# current_stabilizer.net
KiCad netlist of a schematic drawn in Altium Designer
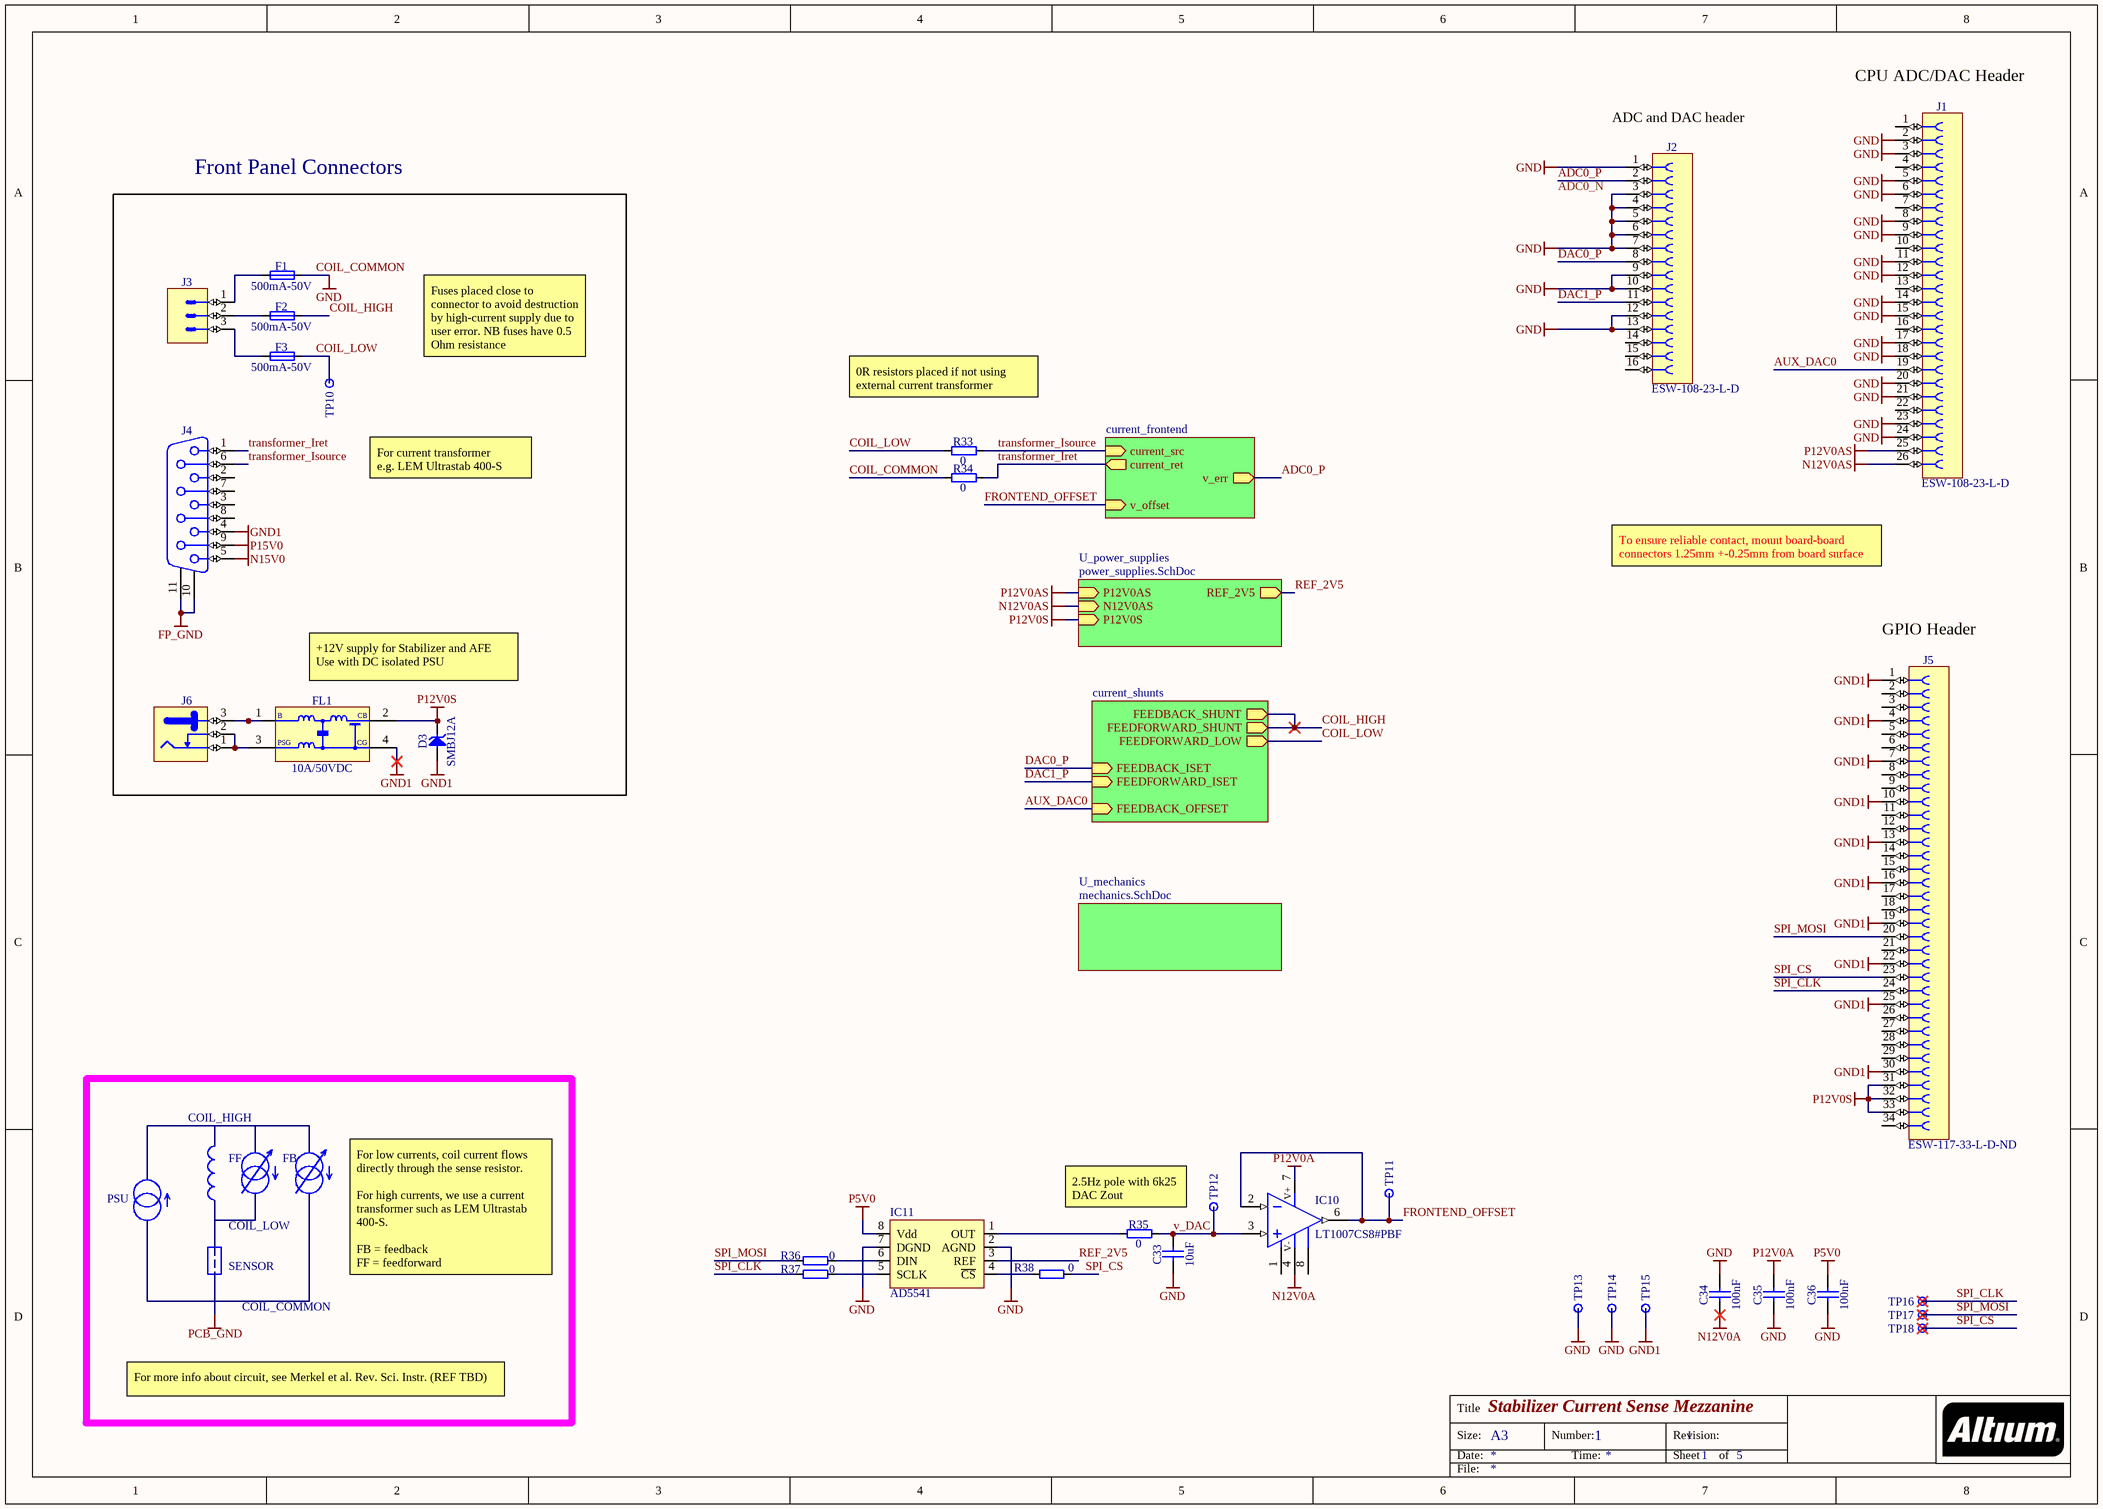
[diagram p0: current_stabilizer.SchDoc]

(export (version "E")
  (design (tool "Eeschema 10.0.6"))
  (components
    (comp (ref "C33")
      (value "10uF")
      (footprint "CAPC2012X95N")
      (description "Non-polarised capacitor")
      (fields
        (field (name "PART NUMBER") "CC0805_10UF_25V_10%_X5R")
        (field (name "VOLTAGE") "25V")
        (field (name "AUTHOR") "CERN DEM JLC")
      )
      (libsource (lib "Capacitors") (part "Capacitor - non polarized"))
    )
    (comp (ref "C34")
      (value "100nF")
      (footprint "CAPC1608X87N")
      (description "Non-polarised capacitor")
      (fields
        (field (name "PART NUMBER") "CC0603_100NF_50V_10%_X7R")
        (field (name "VOLTAGE") "50V")
        (field (name "AUTHOR") "CERN DEM JLC")
      )
      (libsource (lib "Capacitors") (part "Capacitor - non polarized"))
    )
    (comp (ref "C35")
      (value "100nF")
      (footprint "CAPC1608X87N")
      (description "Non-polarised capacitor")
      (fields
        (field (name "PART NUMBER") "CC0603_100NF_50V_10%_X7R")
        (field (name "VOLTAGE") "50V")
        (field (name "AUTHOR") "CERN DEM JLC")
      )
      (libsource (lib "Capacitors") (part "Capacitor - non polarized"))
    )
    (comp (ref "C36")
      (value "100nF")
      (footprint "CAPC1608X87N")
      (description "Non-polarised capacitor")
      (fields
        (field (name "PART NUMBER") "CC0603_100NF_50V_10%_X7R")
        (field (name "VOLTAGE") "50V")
        (field (name "AUTHOR") "CERN DEM JLC")
      )
      (libsource (lib "Capacitors") (part "Capacitor - non polarized"))
    )
    (comp (ref "D3")
      (value "SMBJ12A")
      (footprint "DIOM5336X265N")
      (description "Zener Diode")
      (fields
        (field (name "VOLTAGE") "12V")
        (field (name "POWER") "600W")
        (field (name "AUTHOR") "CERN DEM JLC")
      )
      (libsource (lib "ICs And Semiconductors") (part "Diode Zener"))
    )
    (comp (ref "F1")
      (value "500mA-50V")
      (footprint "FUSC1608X55N")
      (description "Fuse")
      (fields
        (field (name "PART NUMBER") "FUS0603_BOURNS-SF-0603F050-2")
        (field (name "MANUFACTURER") "BOURNS")
        (field (name "AUTHOR") "CERN DEM JLC")
      )
      (libsource (lib "Eletro-mechanical") (part "Fuse"))
    )
    (comp (ref "F2")
      (value "500mA-50V")
      (footprint "FUSC1608X55N")
      (description "Fuse")
      (fields
        (field (name "PART NUMBER") "FUS0603_BOURNS-SF-0603F050-2")
        (field (name "MANUFACTURER") "BOURNS")
        (field (name "AUTHOR") "CERN DEM JLC")
      )
      (libsource (lib "Eletro-mechanical") (part "Fuse"))
    )
    (comp (ref "F3")
      (value "500mA-50V")
      (footprint "FUSC1608X55N")
      (description "Fuse")
      (fields
        (field (name "PART NUMBER") "FUS0603_BOURNS-SF-0603F050-2")
        (field (name "MANUFACTURER") "BOURNS")
        (field (name "AUTHOR") "CERN DEM JLC")
      )
      (libsource (lib "Eletro-mechanical") (part "Fuse"))
    )
    (comp (ref "FL1")
      (value "10A/50VDC")
      (footprint "FIL_MURATA_BNX02")
      (description "Block Type EMIFIL (LC Combined)")
      (fields
        (field (name "PART NUMBER") "FIL_MURATA_BNX022-01L")
        (field (name "MANUFACTURER") "MURATA")
        (field (name "AUTHOR") "CERN DEM JLC")
      )
      (libsource (lib "Inductors & Transformers") (part "FIL_MURATA_BNX02"))
    )
    (comp (ref "IC10")
      (value "LT1007CS8#PBF")
      (footprint "SOIC127P600X175-8N")
      (description "Operational Amplifier with Offset 1-8")
      (fields (field (name "MANUFACTURER") "LINEAR TECHNOLOGY") (field (name "AUTHOR") "CERN DEM JLC"))
      (libsource (lib "ICs And Semiconductors") (part "Operational Amplifier Type3"))
    )
    (comp (ref "IC11")
      (value "AD5541")
      (footprint "library_ICs:so-8")
      (description "16 bit serial DAC")
      (fields
        (field (name "MANUFACTURER") "ANALOG DEVICES")
        (field (name "MANUFACTURER PART NUMBER") "AD5541LRZ")
      )
      (libsource (lib "LIBRARY_SCH") (part "AD5541LRZ"))
    )
    (comp (ref "J1")
      (value "ESW-108-23-L-D")
      (footprint "connectors:ESW-113-23-L-D")
      (description "Connector Elevated Socket 26 POS 2.54mm, 13.59mm height")
      (fields
        (field (name "MANUFACTURER") "Samtec")
        (field (name "MANUFACTURER PART NUMBER") "ESW-108-23-L-D")
      )
      (libsource (lib "connectors") (part "ESW-113-23-L-D"))
    )
    (comp (ref "J2")
      (value "ESW-108-23-L-D")
      (footprint "connectors:ESW-108-23-L-D")
      (description "Connector Elevated Socket 16 POS 2.54mm, 13.59mm height")
      (fields
        (field (name "MANUFACTURER") "Samtec")
        (field (name "MANUFACTURER PART NUMBER") "ESW-108-23-L-D")
      )
      (libsource (lib "connectors") (part "ESW-108-23-L-D"))
    )
    (comp (ref "J3")
      (value "MSTBA")
      (footprint "PHOENIX_1757255")
      (description "Connector 3 Male")
      (fields
        (field (name "PART NUMBER") "PHOENIX_1757255")
        (field (name "MANUFACTURER") "PHOENIX CONTACT")
        (field (name "AUTHOR") "CERN DEM JLC")
      )
      (libsource (lib "Connectors") (part "Connector 3 Male"))
    )
    (comp (ref "J4")
      (value "D-Sub 9F")
      (footprint "FCI_D09S13A4GV00LF")
      (description "Connector D-sub 9 Female")
      (fields
        (field (name "PART NUMBER") "FCI_D09S13A4GV00LF")
        (field (name "MANUFACTURER") "FCI")
        (field (name "AUTHOR") "CERN DEM JLC")
      )
      (libsource (lib "Connectors") (part "Connector D-sub 9 Female"))
    )
    (comp (ref "J5")
      (value "ESW-108-23-L-D")
      (footprint "connectors:ESW-117-23-L-D")
      (description "Connector Elevated Socket 34 POS 2.54mm, 13.59mm height")
      (fields
        (field (name "MANUFACTURER") "Samtec")
        (field (name "MANUFACTURER PART NUMBER") "ESW-117-33-L-D-ND")
      )
      (libsource (lib "connectors") (part "ESW-117-23-L-D"))
    )
    (comp (ref "J6")
      (value "Jack")
      (footprint "Library-connectors:SWITCHCRAFT_L712RA")
      (description "24V /3. 5A, 2.1mm Diameter Pin, SMD DC Power Supply Connector With  Break Contact")
      (fields
        (field (name "PART NUMBER") "SWITCHCRAFT_L712RA")
        (field (name "MANUFACTURER") "SWITCHCRAFT")
        (field (name "AUTHOR") "GK")
      )
      (libsource (lib "LIBRARY_SCH") (part "CON_DC_5A_THT_RA"))
    )
    (comp (ref "R33")
      (value "0")
      (footprint "RESC1608X55N")
      (description "Resistor")
      (fields
        (field (name "PART NUMBER") "R0603_0R_JUMPER")
        (field (name "MANUFACTURER") "GENERIC")
        (field (name "AUTHOR") "CERN DEM JLC")
      )
      (libsource (lib "Resistors") (part "Resistor"))
    )
    (comp (ref "R34")
      (value "0")
      (footprint "RESC1608X55N")
      (description "Resistor")
      (fields
        (field (name "PART NUMBER") "R0603_0R_JUMPER")
        (field (name "MANUFACTURER") "GENERIC")
        (field (name "AUTHOR") "CERN DEM JLC")
      )
      (libsource (lib "Resistors") (part "Resistor"))
    )
    (comp (ref "R35")
      (value "0")
      (footprint "RESC1608X55N")
      (description "Resistor")
      (fields
        (field (name "PART NUMBER") "R0603_0R_JUMPER")
        (field (name "MANUFACTURER") "GENERIC")
        (field (name "AUTHOR") "CERN DEM JLC")
      )
      (libsource (lib "Resistors") (part "Resistor"))
    )
    (comp (ref "R36")
      (value "0")
      (footprint "RESC1608X55N")
      (description "Resistor")
      (fields
        (field (name "PART NUMBER") "R0603_0R_JUMPER")
        (field (name "MANUFACTURER") "GENERIC")
        (field (name "AUTHOR") "CERN DEM JLC")
      )
      (libsource (lib "Resistors") (part "Resistor"))
    )
    (comp (ref "R37")
      (value "0")
      (footprint "RESC1608X55N")
      (description "Resistor")
      (fields
        (field (name "PART NUMBER") "R0603_0R_JUMPER")
        (field (name "MANUFACTURER") "GENERIC")
        (field (name "AUTHOR") "CERN DEM JLC")
      )
      (libsource (lib "Resistors") (part "Resistor"))
    )
    (comp (ref "R38")
      (value "0")
      (footprint "RESC1608X55N")
      (description "Resistor")
      (fields
        (field (name "PART NUMBER") "R0603_0R_JUMPER")
        (field (name "MANUFACTURER") "GENERIC")
        (field (name "AUTHOR") "CERN DEM JLC")
      )
      (libsource (lib "Resistors") (part "Resistor"))
    )
    (comp (ref "TP10")
      (value "Test Point")
      (footprint "TPS127")
      (fields (field (name "PART NUMBER") "SMD_PAD_1.27X1.27MM") (field (name "AUTHOR") "CERN DEM JLC"))
      (libsource (lib "Eletro-mechanical") (part "Test Point"))
    )
    (comp (ref "TP11")
      (value "Test Point")
      (footprint "TPS127")
      (fields (field (name "PART NUMBER") "SMD_PAD_1.27X1.27MM") (field (name "AUTHOR") "CERN DEM JLC"))
      (libsource (lib "Eletro-mechanical") (part "Test Point"))
    )
    (comp (ref "TP12")
      (value "Test Point")
      (footprint "TPS127")
      (fields (field (name "PART NUMBER") "SMD_PAD_1.27X1.27MM") (field (name "AUTHOR") "CERN DEM JLC"))
      (libsource (lib "Eletro-mechanical") (part "Test Point"))
    )
    (comp (ref "TP13")
      (value "Test Point")
      (footprint "TPS127")
      (fields (field (name "PART NUMBER") "SMD_PAD_1.27X1.27MM") (field (name "AUTHOR") "CERN DEM JLC"))
      (libsource (lib "Eletro-mechanical") (part "Test Point"))
    )
    (comp (ref "TP14")
      (value "Test Point")
      (footprint "TPS127")
      (fields (field (name "PART NUMBER") "SMD_PAD_1.27X1.27MM") (field (name "AUTHOR") "CERN DEM JLC"))
      (libsource (lib "Eletro-mechanical") (part "Test Point"))
    )
    (comp (ref "TP15")
      (value "Test Point")
      (footprint "TPS127")
      (fields (field (name "PART NUMBER") "SMD_PAD_1.27X1.27MM") (field (name "AUTHOR") "CERN DEM JLC"))
      (libsource (lib "Eletro-mechanical") (part "Test Point"))
    )
    (comp (ref "TP16")
      (value "Test Point")
      (footprint "TPS127")
      (fields (field (name "PART NUMBER") "SMD_PAD_1.27X1.27MM") (field (name "AUTHOR") "CERN DEM JLC"))
      (libsource (lib "Eletro-mechanical") (part "Test Point"))
    )
    (comp (ref "TP17")
      (value "Test Point")
      (footprint "TPS127")
      (fields (field (name "PART NUMBER") "SMD_PAD_1.27X1.27MM") (field (name "AUTHOR") "CERN DEM JLC"))
      (libsource (lib "Eletro-mechanical") (part "Test Point"))
    )
    (comp (ref "TP18")
      (value "Test Point")
      (footprint "TPS127")
      (fields (field (name "PART NUMBER") "SMD_PAD_1.27X1.27MM") (field (name "AUTHOR") "CERN DEM JLC"))
      (libsource (lib "Eletro-mechanical") (part "Test Point"))
    )
  )
  (nets
    (net (code "1") (name "/ADC0_P") (class "Default")
      (node (ref "J2") (pin "2") (pinfunction "2_2") (pintype "bidirectional"))
    )
    (net (code "2") (name "/AUX_DAC0") (class "Default")
      (node (ref "J1") (pin "19") (pinfunction "19_19") (pintype "bidirectional"))
    )
    (net (code "3") (name "/COIL_HIGH") (class "Default")
      (node (ref "F2") (pin "1") (pinfunction "1_1") (pintype "passive+no_connect"))
    )
    (net (code "4") (name "/COIL_LOW") (class "Default")
      (node (ref "F3") (pin "1") (pinfunction "1_1") (pintype "passive"))
      (node (ref "R33") (pin "1") (pinfunction "1_1") (pintype "passive"))
      (node (ref "TP10") (pin "1") (pinfunction "1_1") (pintype "bidirectional"))
    )
    (net (code "5") (name "/DAC0_P") (class "Default")
      (node (ref "J2") (pin "8") (pinfunction "8_8") (pintype "bidirectional"))
    )
    (net (code "6") (name "/DAC1_P") (class "Default")
      (node (ref "J2") (pin "11") (pinfunction "11_11") (pintype "bidirectional"))
    )
    (net (code "7") (name "/FRONTEND_OFFSET") (class "Default")
      (node (ref "IC10") (pin "2") (pinfunction "IN-_2") (pintype "input"))
      (node (ref "IC10") (pin "6") (pinfunction "OUT_6") (pintype "output"))
      (node (ref "TP11") (pin "1") (pinfunction "1_1") (pintype "bidirectional"))
    )
    (net (code "8") (name "/REF_2V5") (class "Default")
      (node (ref "IC11") (pin "3") (pinfunction "REF_3") (pintype "passive"))
    )
    (net (code "9") (name "/SPI_CLK") (class "Default")
      (node (ref "J5") (pin "24") (pinfunction "24_24") (pintype "bidirectional"))
      (node (ref "R37") (pin "1") (pinfunction "1_1") (pintype "passive"))
      (node (ref "TP16") (pin "1") (pinfunction "1_1") (pintype "bidirectional"))
    )
    (net (code "10") (name "/SPI_CS") (class "Default")
      (node (ref "J5") (pin "23") (pinfunction "23_23") (pintype "bidirectional"))
      (node (ref "R38") (pin "2") (pinfunction "2_2") (pintype "passive"))
      (node (ref "TP18") (pin "1") (pinfunction "1_1") (pintype "bidirectional"))
    )
    (net (code "11") (name "/SPI_MOSI") (class "Default")
      (node (ref "J5") (pin "20") (pinfunction "20_20") (pintype "bidirectional"))
      (node (ref "R36") (pin "1") (pinfunction "1_1") (pintype "passive"))
      (node (ref "TP17") (pin "1") (pinfunction "1_1") (pintype "bidirectional"))
    )
    (net (code "12") (name "/transformer_Iret") (class "Default")
      (node (ref "J4") (pin "1") (pinfunction "1_1") (pintype "bidirectional"))
      (node (ref "R34") (pin "2") (pinfunction "2_2") (pintype "passive"))
    )
    (net (code "13") (name "/transformer_Isource") (class "Default")
      (node (ref "J4") (pin "6") (pinfunction "6_6") (pintype "bidirectional"))
      (node (ref "R33") (pin "2") (pinfunction "2_2") (pintype "passive"))
    )
    (net (code "14") (name "/v_DAC") (class "Default")
      (node (ref "C33") (pin "2") (pinfunction "2_2") (pintype "passive"))
      (node (ref "IC10") (pin "3") (pinfunction "IN+_3") (pintype "input"))
      (node (ref "R35") (pin "2") (pinfunction "2_2") (pintype "passive"))
      (node (ref "TP12") (pin "1") (pinfunction "1_1") (pintype "bidirectional"))
    )
    (net (code "15") (name "FP_GND") (class "Default")
      (node (ref "J4") (pin "10") (pinfunction "10_10") (pintype "passive"))
      (node (ref "J4") (pin "11") (pinfunction "11_11") (pintype "passive"))
    )
    (net (code "16") (name "GND") (class "Default")
      (node (ref "C33") (pin "1") (pinfunction "1_1") (pintype "passive"))
      (node (ref "C34") (pin "2") (pinfunction "2_2") (pintype "passive"))
      (node (ref "C35") (pin "1") (pinfunction "1_1") (pintype "passive"))
      (node (ref "C36") (pin "1") (pinfunction "1_1") (pintype "passive"))
      (node (ref "F1") (pin "1") (pinfunction "1_1") (pintype "passive"))
      (node (ref "IC11") (pin "2") (pinfunction "AGND_2") (pintype "passive"))
      (node (ref "IC11") (pin "7") (pinfunction "DGND_7") (pintype "passive"))
      (node (ref "J1") (pin "11") (pinfunction "11_11") (pintype "bidirectional"))
      (node (ref "J1") (pin "12") (pinfunction "12_12") (pintype "bidirectional"))
      (node (ref "J1") (pin "14") (pinfunction "14_14") (pintype "bidirectional"))
      (node (ref "J1") (pin "15") (pinfunction "15_15") (pintype "bidirectional"))
      (node (ref "J1") (pin "17") (pinfunction "17_17") (pintype "bidirectional"))
      (node (ref "J1") (pin "18") (pinfunction "18_18") (pintype "bidirectional"))
      (node (ref "J1") (pin "2") (pinfunction "2_2") (pintype "bidirectional"))
      (node (ref "J1") (pin "20") (pinfunction "20_20") (pintype "bidirectional"))
      (node (ref "J1") (pin "21") (pinfunction "21_21") (pintype "bidirectional"))
      (node (ref "J1") (pin "23") (pinfunction "23_23") (pintype "bidirectional"))
      (node (ref "J1") (pin "24") (pinfunction "24_24") (pintype "bidirectional"))
      (node (ref "J1") (pin "3") (pinfunction "3_3") (pintype "bidirectional"))
      (node (ref "J1") (pin "5") (pinfunction "5_5") (pintype "bidirectional"))
      (node (ref "J1") (pin "6") (pinfunction "6_6") (pintype "bidirectional"))
      (node (ref "J1") (pin "8") (pinfunction "8_8") (pintype "bidirectional"))
      (node (ref "J1") (pin "9") (pinfunction "9_9") (pintype "bidirectional"))
      (node (ref "J2") (pin "1") (pinfunction "1_1") (pintype "bidirectional"))
      (node (ref "J2") (pin "10") (pinfunction "10_10") (pintype "bidirectional"))
      (node (ref "J2") (pin "12") (pinfunction "12_12") (pintype "bidirectional"))
      (node (ref "J2") (pin "13") (pinfunction "13_13") (pintype "bidirectional"))
      (node (ref "J2") (pin "3") (pinfunction "3_3") (pintype "bidirectional"))
      (node (ref "J2") (pin "4") (pinfunction "4_4") (pintype "bidirectional"))
      (node (ref "J2") (pin "5") (pinfunction "5_5") (pintype "bidirectional"))
      (node (ref "J2") (pin "6") (pinfunction "6_6") (pintype "bidirectional"))
      (node (ref "J2") (pin "7") (pinfunction "7_7") (pintype "bidirectional"))
      (node (ref "J2") (pin "9") (pinfunction "9_9") (pintype "bidirectional"))
      (node (ref "R34") (pin "1") (pinfunction "1_1") (pintype "passive"))
      (node (ref "TP13") (pin "1") (pinfunction "1_1") (pintype "bidirectional"))
      (node (ref "TP14") (pin "1") (pinfunction "1_1") (pintype "bidirectional"))
    )
    (net (code "17") (name "GND1") (class "Default")
      (node (ref "D3") (pin "2") (pinfunction "A_2") (pintype "passive"))
      (node (ref "FL1") (pin "4") (pinfunction "CG_4") (pintype "passive"))
      (node (ref "J4") (pin "4") (pinfunction "4_4") (pintype "bidirectional"))
      (node (ref "J5") (pin "1") (pinfunction "1_1") (pintype "bidirectional"))
      (node (ref "J5") (pin "10") (pinfunction "10_10") (pintype "bidirectional"))
      (node (ref "J5") (pin "13") (pinfunction "13_13") (pintype "bidirectional"))
      (node (ref "J5") (pin "16") (pinfunction "16_16") (pintype "bidirectional"))
      (node (ref "J5") (pin "19") (pinfunction "19_19") (pintype "bidirectional"))
      (node (ref "J5") (pin "22") (pinfunction "22_22") (pintype "bidirectional"))
      (node (ref "J5") (pin "25") (pinfunction "25_25") (pintype "bidirectional"))
      (node (ref "J5") (pin "30") (pinfunction "30_30") (pintype "bidirectional"))
      (node (ref "J5") (pin "4") (pinfunction "4_4") (pintype "bidirectional"))
      (node (ref "J5") (pin "7") (pinfunction "7_7") (pintype "bidirectional"))
      (node (ref "TP15") (pin "1") (pinfunction "1_1") (pintype "bidirectional"))
    )
    (net (code "18") (name "N12V0A") (class "Default")
      (node (ref "C34") (pin "1") (pinfunction "1_1") (pintype "passive"))
      (node (ref "IC10") (pin "4") (pinfunction "V-_4") (pintype "power_in"))
    )
    (net (code "19") (name "N12V0AS") (class "Default")
      (node (ref "J1") (pin "26") (pinfunction "26_26") (pintype "bidirectional"))
    )
    (net (code "20") (name "N15V0") (class "Default")
      (node (ref "J4") (pin "5") (pinfunction "5_5") (pintype "bidirectional"))
    )
    (net (code "21") (name "Net-(F1-Pad2)") (class "Default")
      (node (ref "F1") (pin "2") (pinfunction "2_2") (pintype "passive"))
      (node (ref "J3") (pin "1") (pinfunction "1_1") (pintype "bidirectional"))
    )
    (net (code "22") (name "Net-(F2-Pad2)") (class "Default")
      (node (ref "F2") (pin "2") (pinfunction "2_2") (pintype "passive"))
      (node (ref "J3") (pin "2") (pinfunction "2_2") (pintype "bidirectional"))
    )
    (net (code "23") (name "Net-(F3-Pad2)") (class "Default")
      (node (ref "F3") (pin "2") (pinfunction "2_2") (pintype "passive"))
      (node (ref "J3") (pin "3") (pinfunction "3_3") (pintype "bidirectional"))
    )
    (net (code "24") (name "Net-(FL1-B)") (class "Default")
      (node (ref "FL1") (pin "1") (pinfunction "B_1") (pintype "passive"))
      (node (ref "J6") (pin "3") (pinfunction "3_3") (pintype "bidirectional"))
    )
    (net (code "25") (name "Net-(FL1-PSG)") (class "Default")
      (node (ref "FL1") (pin "3") (pinfunction "PSG_3") (pintype "passive"))
      (node (ref "J6") (pin "1") (pinfunction "1_1") (pintype "bidirectional"))
      (node (ref "J6") (pin "2") (pinfunction "2_2") (pintype "bidirectional"))
    )
    (net (code "26") (name "Net-(IC11-DIN)") (class "Default")
      (node (ref "IC11") (pin "6") (pinfunction "DIN_6") (pintype "passive"))
      (node (ref "R36") (pin "2") (pinfunction "2_2") (pintype "passive"))
    )
    (net (code "27") (name "Net-(IC11-OUT)") (class "Default")
      (node (ref "IC11") (pin "1") (pinfunction "OUT_1") (pintype "passive"))
      (node (ref "R35") (pin "1") (pinfunction "1_1") (pintype "passive"))
    )
    (net (code "28") (name "Net-(IC11-SCLK)") (class "Default")
      (node (ref "IC11") (pin "5") (pinfunction "SCLK_5") (pintype "passive"))
      (node (ref "R37") (pin "2") (pinfunction "2_2") (pintype "passive"))
    )
    (net (code "29") (name "Net-(IC11-~{CS})") (class "Default")
      (node (ref "IC11") (pin "4") (pinfunction "~{CS}_4") (pintype "passive"))
      (node (ref "R38") (pin "1") (pinfunction "1_1") (pintype "passive"))
    )
    (net (code "30") (name "P5V0") (class "Default")
      (node (ref "C36") (pin "2") (pinfunction "2_2") (pintype "passive"))
      (node (ref "IC11") (pin "8") (pinfunction "Vdd_8") (pintype "passive"))
    )
    (net (code "31") (name "P12V0A") (class "Default")
      (node (ref "C35") (pin "2") (pinfunction "2_2") (pintype "passive"))
      (node (ref "IC10") (pin "7") (pinfunction "V+_7") (pintype "power_in"))
    )
    (net (code "32") (name "P12V0AS") (class "Default")
      (node (ref "J1") (pin "25") (pinfunction "25_25") (pintype "bidirectional"))
    )
    (net (code "33") (name "P12V0S") (class "Default")
      (node (ref "D3") (pin "1") (pinfunction "C_1") (pintype "passive"))
      (node (ref "FL1") (pin "2") (pinfunction "CB_2") (pintype "passive"))
      (node (ref "J5") (pin "31") (pinfunction "31_31") (pintype "bidirectional"))
      (node (ref "J5") (pin "32") (pinfunction "32_32") (pintype "bidirectional"))
      (node (ref "J5") (pin "33") (pinfunction "33_33") (pintype "bidirectional"))
    )
    (net (code "34") (name "P15V0") (class "Default")
      (node (ref "J4") (pin "9") (pinfunction "9_9") (pintype "bidirectional"))
    )
    (net (code "35") (name "unconnected-(IC10-OFFSET-Pad1)") (class "Default")
      (node (ref "IC10") (pin "1") (pinfunction "OFFSET_1") (pintype "passive"))
    )
    (net (code "36") (name "unconnected-(IC10-OFFSET-Pad8)") (class "Default")
      (node (ref "IC10") (pin "8") (pinfunction "OFFSET_8") (pintype "passive"))
    )
    (net (code "37") (name "unconnected-(J1-Pad1)") (class "Default")
      (node (ref "J1") (pin "1") (pinfunction "1_1") (pintype "bidirectional"))
    )
    (net (code "38") (name "unconnected-(J1-Pad4)") (class "Default")
      (node (ref "J1") (pin "4") (pinfunction "4_4") (pintype "bidirectional"))
    )
    (net (code "39") (name "unconnected-(J1-Pad7)") (class "Default")
      (node (ref "J1") (pin "7") (pinfunction "7_7") (pintype "bidirectional"))
    )
    (net (code "40") (name "unconnected-(J1-Pad10)") (class "Default")
      (node (ref "J1") (pin "10") (pinfunction "10_10") (pintype "bidirectional"))
    )
    (net (code "41") (name "unconnected-(J1-Pad13)") (class "Default")
      (node (ref "J1") (pin "13") (pinfunction "13_13") (pintype "bidirectional"))
    )
    (net (code "42") (name "unconnected-(J1-Pad16)") (class "Default")
      (node (ref "J1") (pin "16") (pinfunction "16_16") (pintype "bidirectional"))
    )
    (net (code "43") (name "unconnected-(J1-Pad22)") (class "Default")
      (node (ref "J1") (pin "22") (pinfunction "22_22") (pintype "bidirectional"))
    )
    (net (code "44") (name "unconnected-(J2-Pad14)") (class "Default")
      (node (ref "J2") (pin "14") (pinfunction "14_14") (pintype "bidirectional"))
    )
    (net (code "45") (name "unconnected-(J2-Pad15)") (class "Default")
      (node (ref "J2") (pin "15") (pinfunction "15_15") (pintype "bidirectional"))
    )
    (net (code "46") (name "unconnected-(J2-Pad16)") (class "Default")
      (node (ref "J2") (pin "16") (pinfunction "16_16") (pintype "bidirectional"))
    )
    (net (code "47") (name "unconnected-(J4-Pad2)") (class "Default")
      (node (ref "J4") (pin "2") (pinfunction "2_2") (pintype "bidirectional"))
    )
    (net (code "48") (name "unconnected-(J4-Pad3)") (class "Default")
      (node (ref "J4") (pin "3") (pinfunction "3_3") (pintype "bidirectional"))
    )
    (net (code "49") (name "unconnected-(J4-Pad7)") (class "Default")
      (node (ref "J4") (pin "7") (pinfunction "7_7") (pintype "bidirectional"))
    )
    (net (code "50") (name "unconnected-(J4-Pad8)") (class "Default")
      (node (ref "J4") (pin "8") (pinfunction "8_8") (pintype "bidirectional"))
    )
    (net (code "51") (name "unconnected-(J5-Pad2)") (class "Default")
      (node (ref "J5") (pin "2") (pinfunction "2_2") (pintype "bidirectional"))
    )
    (net (code "52") (name "unconnected-(J5-Pad3)") (class "Default")
      (node (ref "J5") (pin "3") (pinfunction "3_3") (pintype "bidirectional"))
    )
    (net (code "53") (name "unconnected-(J5-Pad5)") (class "Default")
      (node (ref "J5") (pin "5") (pinfunction "5_5") (pintype "bidirectional"))
    )
    (net (code "54") (name "unconnected-(J5-Pad6)") (class "Default")
      (node (ref "J5") (pin "6") (pinfunction "6_6") (pintype "bidirectional"))
    )
    (net (code "55") (name "unconnected-(J5-Pad8)") (class "Default")
      (node (ref "J5") (pin "8") (pinfunction "8_8") (pintype "bidirectional"))
    )
    (net (code "56") (name "unconnected-(J5-Pad9)") (class "Default")
      (node (ref "J5") (pin "9") (pinfunction "9_9") (pintype "bidirectional"))
    )
    (net (code "57") (name "unconnected-(J5-Pad11)") (class "Default")
      (node (ref "J5") (pin "11") (pinfunction "11_11") (pintype "bidirectional"))
    )
    (net (code "58") (name "unconnected-(J5-Pad12)") (class "Default")
      (node (ref "J5") (pin "12") (pinfunction "12_12") (pintype "bidirectional"))
    )
    (net (code "59") (name "unconnected-(J5-Pad14)") (class "Default")
      (node (ref "J5") (pin "14") (pinfunction "14_14") (pintype "bidirectional"))
    )
    (net (code "60") (name "unconnected-(J5-Pad15)") (class "Default")
      (node (ref "J5") (pin "15") (pinfunction "15_15") (pintype "bidirectional"))
    )
    (net (code "61") (name "unconnected-(J5-Pad17)") (class "Default")
      (node (ref "J5") (pin "17") (pinfunction "17_17") (pintype "bidirectional"))
    )
    (net (code "62") (name "unconnected-(J5-Pad18)") (class "Default")
      (node (ref "J5") (pin "18") (pinfunction "18_18") (pintype "bidirectional"))
    )
    (net (code "63") (name "unconnected-(J5-Pad21)") (class "Default")
      (node (ref "J5") (pin "21") (pinfunction "21_21") (pintype "bidirectional"))
    )
    (net (code "64") (name "unconnected-(J5-Pad26)") (class "Default")
      (node (ref "J5") (pin "26") (pinfunction "26_26") (pintype "bidirectional"))
    )
    (net (code "65") (name "unconnected-(J5-Pad27)") (class "Default")
      (node (ref "J5") (pin "27") (pinfunction "27_27") (pintype "bidirectional"))
    )
    (net (code "66") (name "unconnected-(J5-Pad28)") (class "Default")
      (node (ref "J5") (pin "28") (pinfunction "28_28") (pintype "bidirectional"))
    )
    (net (code "67") (name "unconnected-(J5-Pad29)") (class "Default")
      (node (ref "J5") (pin "29") (pinfunction "29_29") (pintype "bidirectional"))
    )
    (net (code "68") (name "unconnected-(J5-Pad34)") (class "Default")
      (node (ref "J5") (pin "34") (pinfunction "34_34") (pintype "bidirectional"))
    )
  )
)
